# B36-V1_2.net
KiCad netlist of a schematic drawn in Altium Designer
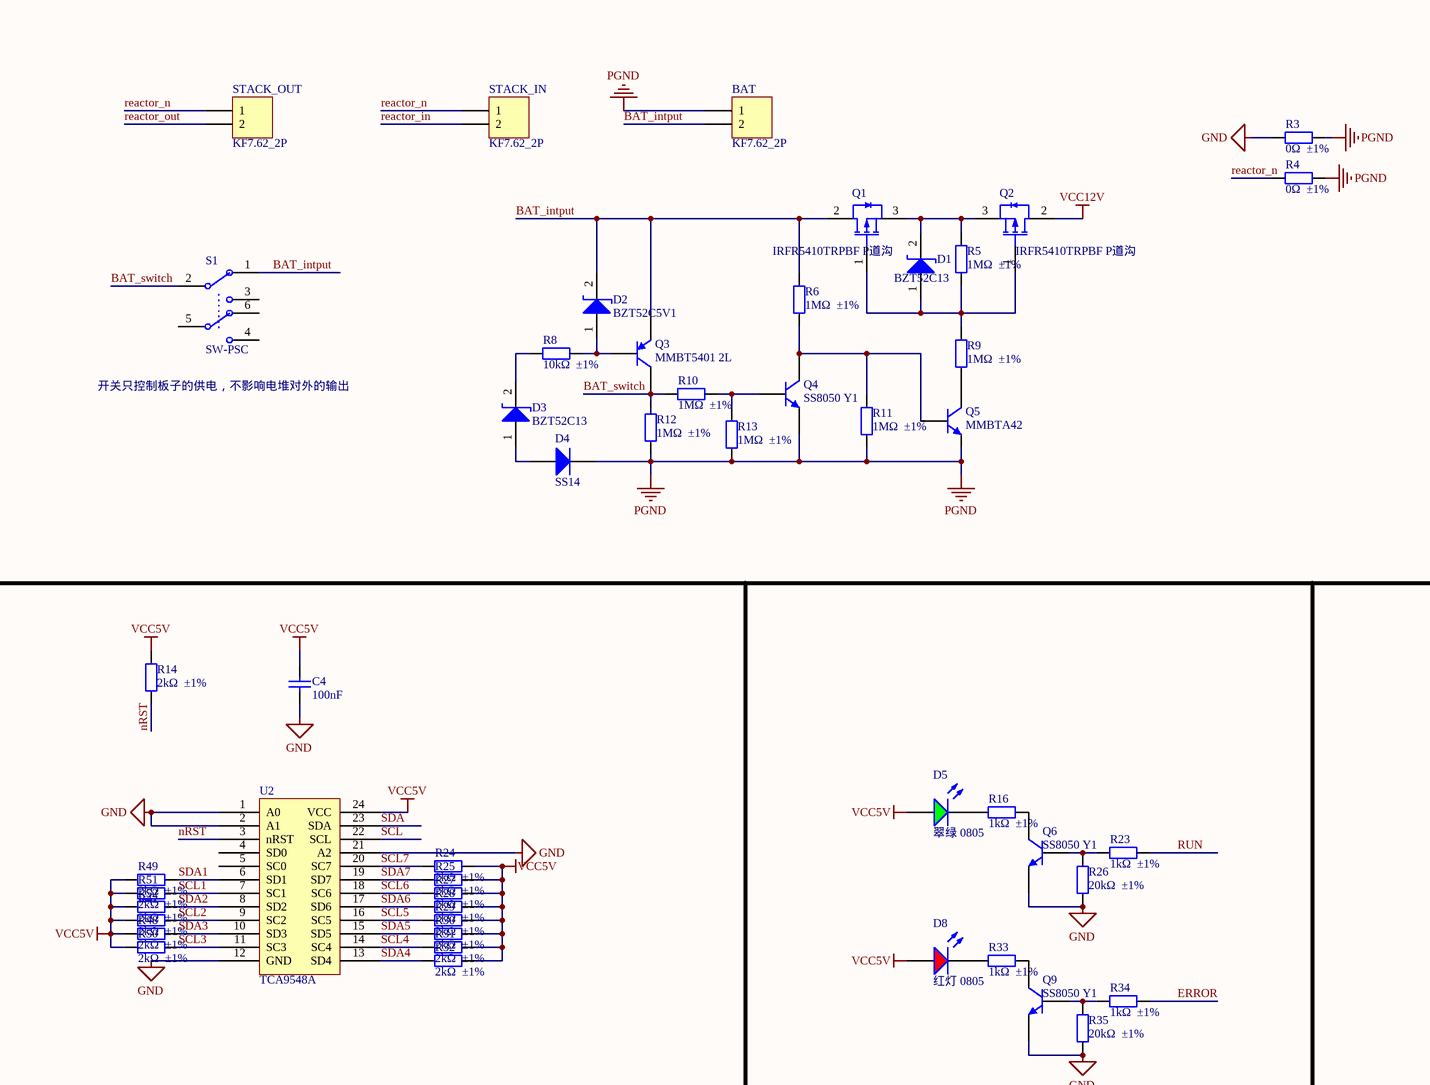
[diagram p0: B36-V1.2.SchDoc, top left]
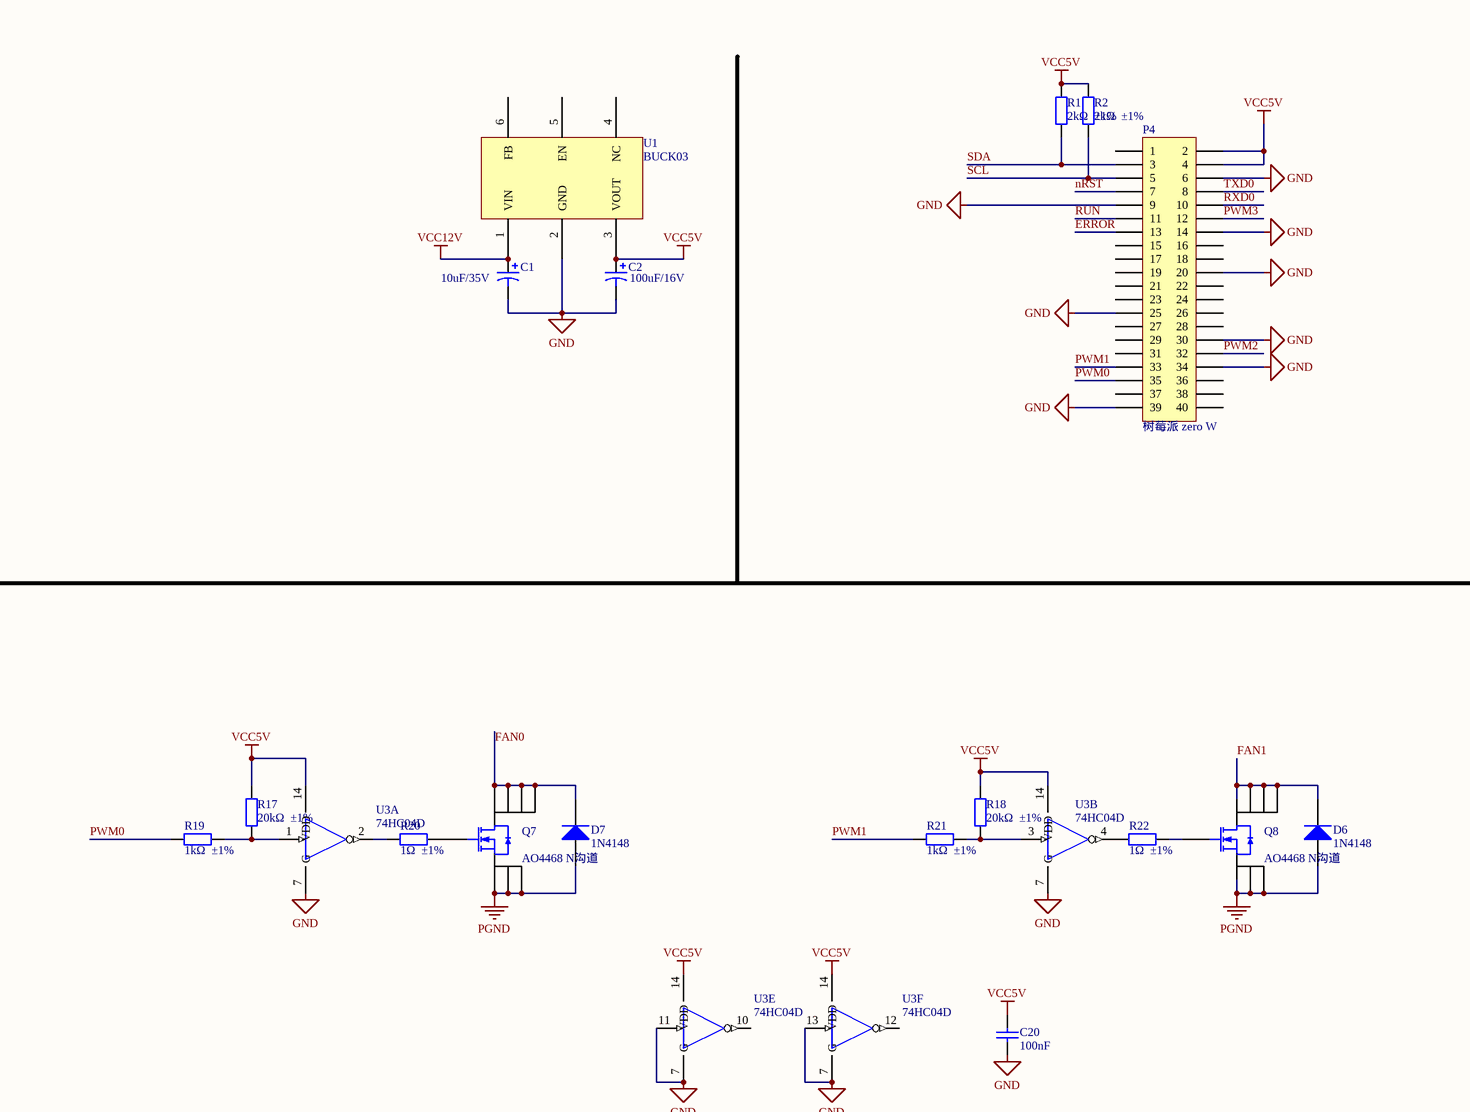
[diagram p1: B36-V1.2.SchDoc, top right]
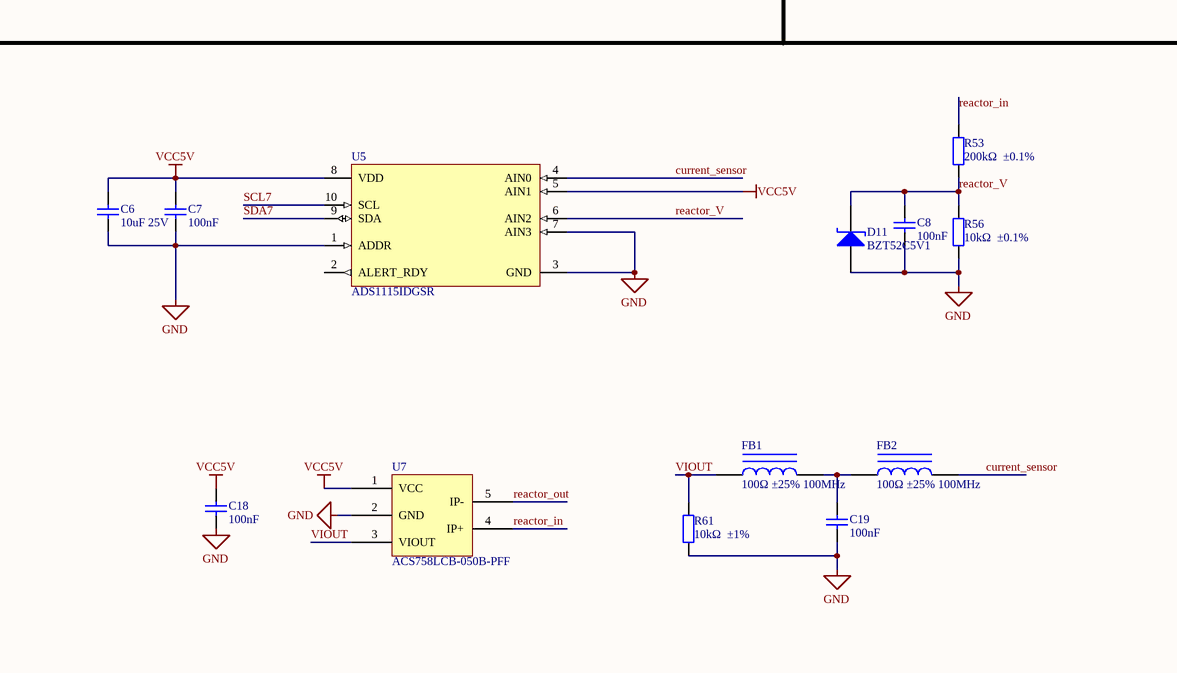
[diagram p2: B36-V1.2.SchDoc, bottom left]
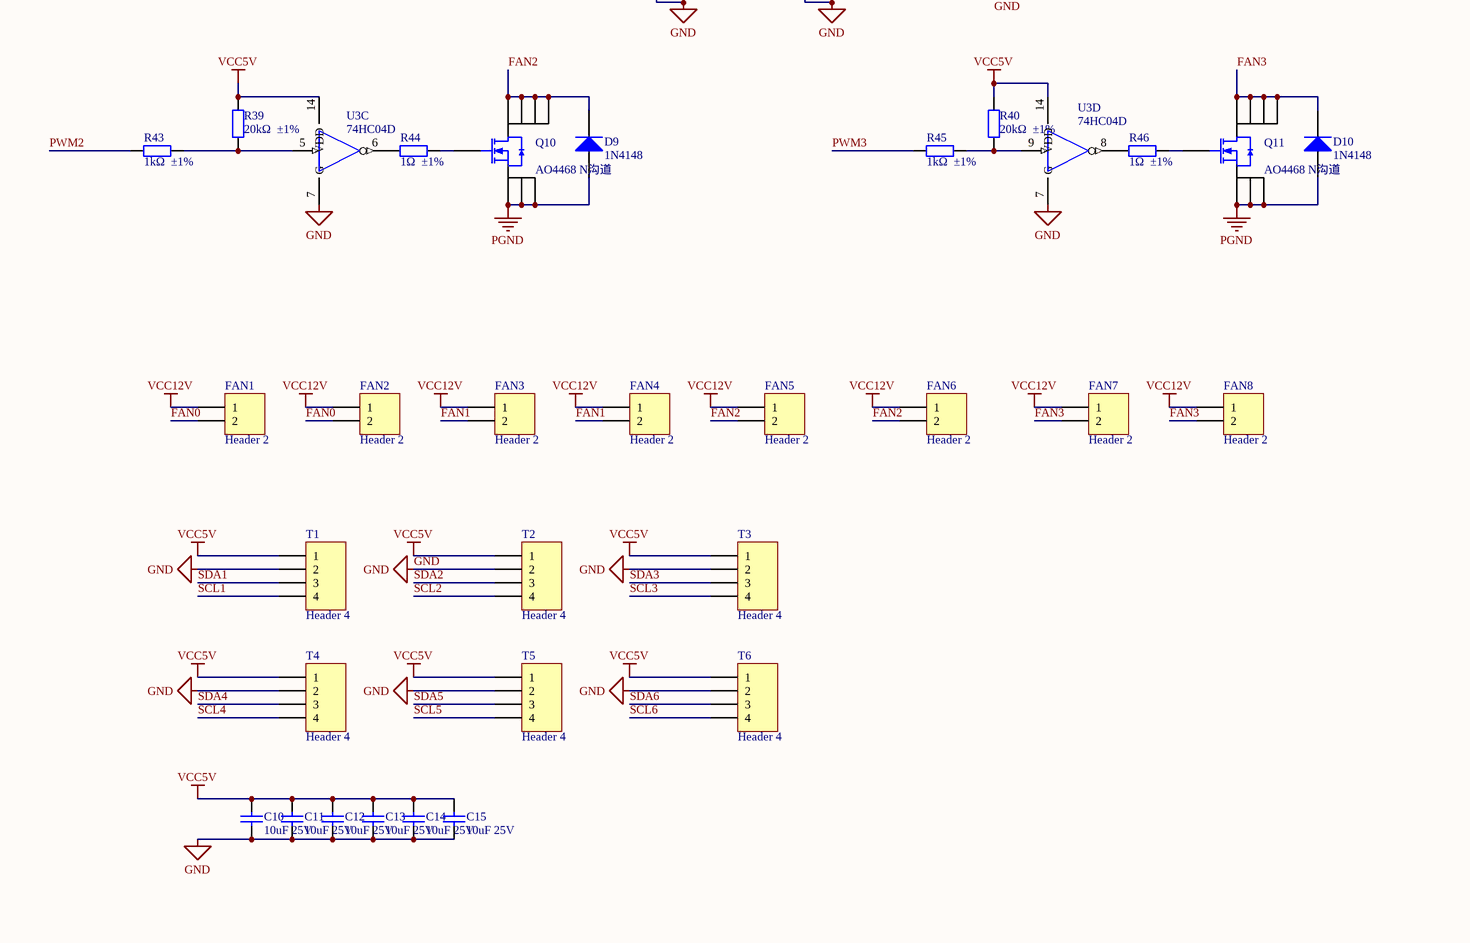
[diagram p3: B36-V1.2.SchDoc, bottom right]

(export (version "E")
  (design (tool "Eeschema 10.0.6"))
  (components
    (comp (ref "BAT")
      (value "KF7.62_2P")
      (footprint "KF7.62_2P")
      (description "Header, 2-Pin")
      (fields (field (name "PUBLISHER") "Altium Limited"))
      (libsource (lib "Miscellaneous Connectors") (part "Header 2"))
    )
    (comp (ref "C1")
      (value "10uF/35V")
      (footprint "CASE-C_6032")
      (description "Polarized Capacitor (Radial)")
      (fields (field (name "PUBLISHER") "Altium Limited"))
      (libsource (lib "MainBoard") (part "Cap Pol1"))
    )
    (comp (ref "C2")
      (value "100uF/16V")
      (footprint "CASE-C_6032")
      (description "Polarized Capacitor (Radial)")
      (fields (field (name "PUBLISHER") "Altium Limited"))
      (libsource (lib "MainBoard") (part "Cap Pol1"))
    )
    (comp (ref "C4")
      (value "100nF")
      (footprint "0603_C")
      (description "贴片电容")
      (libsource (lib "Cap") (part "0603 1.0pF (010) 0.25pF 50V"))
    )
    (comp (ref "C6")
      (value "10uF 25V")
      (footprint "0603_C")
      (description "贴片电容")
      (libsource (lib "Cap") (part "0805 6.8nF (682) 10% 50V"))
    )
    (comp (ref "C7")
      (value "100nF")
      (footprint "0603_C")
      (description "贴片电容")
      (libsource (lib "Cap") (part "0603 1.0pF (010) 0.25pF 50V"))
    )
    (comp (ref "C8")
      (value "100nF")
      (footprint "0603_C")
      (description "贴片电容")
      (libsource (lib "Cap") (part "0603 1.0pF (010) 0.25pF 50V"))
    )
    (comp (ref "C10")
      (value "10uF 25V")
      (footprint "0805_C")
      (description "贴片电容")
      (libsource (lib "Cap") (part "0805 6.8nF (682) 10% 50V"))
    )
    (comp (ref "C11")
      (value "10uF 25V")
      (footprint "0805_C")
      (description "贴片电容")
      (libsource (lib "Cap") (part "0805 6.8nF (682) 10% 50V"))
    )
    (comp (ref "C12")
      (value "10uF 25V")
      (footprint "0805_C")
      (description "贴片电容")
      (libsource (lib "Cap") (part "0805 6.8nF (682) 10% 50V"))
    )
    (comp (ref "C13")
      (value "10uF 25V")
      (footprint "0805_C")
      (description "贴片电容")
      (libsource (lib "Cap") (part "0805 6.8nF (682) 10% 50V"))
    )
    (comp (ref "C14")
      (value "10uF 25V")
      (footprint "0805_C")
      (description "贴片电容")
      (libsource (lib "Cap") (part "0805 6.8nF (682) 10% 50V"))
    )
    (comp (ref "C15")
      (value "10uF 25V")
      (footprint "0805_C")
      (description "贴片电容")
      (libsource (lib "Cap") (part "0805 6.8nF (682) 10% 50V"))
    )
    (comp (ref "C18")
      (value "100nF")
      (footprint "0603_C")
      (description "贴片电容")
      (libsource (lib "Cap") (part "0603 1.0pF (010) 0.25pF 50V"))
    )
    (comp (ref "C19")
      (value "100nF")
      (footprint "0603_C")
      (description "贴片电容")
      (libsource (lib "Cap") (part "0603 1.0pF (010) 0.25pF 50V"))
    )
    (comp (ref "C20")
      (value "100nF")
      (footprint "0603_C")
      (description "贴片电容")
      (libsource (lib "Cap") (part "0603 1.0pF (010) 0.25pF 50V"))
    )
    (comp (ref "D1")
      (value "BZT52C13")
      (footprint "sod-123")
      (description "稳压二极管")
      (fields (field (name "PUBLISHER") "Altium Limited"))
      (libsource (lib "Diode") (part "Diode-Z"))
    )
    (comp (ref "D2")
      (value "BZT52C5V1")
      (footprint "sod-123")
      (description "稳压二极管")
      (fields (field (name "PUBLISHER") "Altium Limited"))
      (libsource (lib "Diode") (part "Diode-Z"))
    )
    (comp (ref "D3")
      (value "BZT52C13")
      (footprint "sod-123")
      (description "稳压二极管")
      (fields (field (name "PUBLISHER") "Altium Limited"))
      (libsource (lib "Diode") (part "Diode-Z"))
    )
    (comp (ref "D4")
      (value "SS14")
      (footprint "sod-123")
      (description "二极管")
      (libsource (lib "Diode") (part "SMA(DO-214AC) SS54"))
    )
    (comp (ref "D5")
      (value "翠绿 0805")
      (footprint "0805_LED_S1")
      (description "发光二极管")
      (libsource (lib "LED") (part "0805 翠绿"))
    )
    (comp (ref "D6")
      (value "1N4148")
      (footprint "SOD-123")
      (description "肖特基二极管")
      (libsource (lib "Diode") (part "SOD-123 B5819W  SL"))
    )
    (comp (ref "D7")
      (value "1N4148")
      (footprint "SOD-123")
      (description "肖特基二极管")
      (libsource (lib "Diode") (part "SOD-123 B5819W  SL"))
    )
    (comp (ref "D8")
      (value "红灯 0805")
      (footprint "0805_LED_S1")
      (description "发光二极管")
      (libsource (lib "LED") (part "0805 红灯"))
    )
    (comp (ref "D9")
      (value "1N4148")
      (footprint "SOD-123")
      (description "肖特基二极管")
      (libsource (lib "Diode") (part "SOD-123 B5819W  SL"))
    )
    (comp (ref "D10")
      (value "1N4148")
      (footprint "SOD-123")
      (description "肖特基二极管")
      (libsource (lib "Diode") (part "SOD-123 B5819W  SL"))
    )
    (comp (ref "D11")
      (value "BZT52C5V1")
      (footprint "sod-123")
      (description "稳压二极管")
      (fields (field (name "PUBLISHER") "Altium Limited"))
      (libsource (lib "") (part "Diode-Z_1"))
    )
    (comp (ref "FAN1")
      (value "Header 2")
      (footprint "xh2.54_2p")
      (description "Header, 2-Pin")
      (fields (field (name "PUBLISHER") "Altium Limited"))
      (libsource (lib "Miscellaneous Connectors") (part "Header 2"))
    )
    (comp (ref "FAN2")
      (value "Header 2")
      (footprint "xh2.54_2p")
      (description "Header, 2-Pin")
      (fields (field (name "PUBLISHER") "Altium Limited"))
      (libsource (lib "Miscellaneous Connectors") (part "Header 2"))
    )
    (comp (ref "FAN3")
      (value "Header 2")
      (footprint "xh2.54_2p")
      (description "Header, 2-Pin")
      (fields (field (name "PUBLISHER") "Altium Limited"))
      (libsource (lib "Miscellaneous Connectors") (part "Header 2"))
    )
    (comp (ref "FAN4")
      (value "Header 2")
      (footprint "xh2.54_2p")
      (description "Header, 2-Pin")
      (fields (field (name "PUBLISHER") "Altium Limited"))
      (libsource (lib "Miscellaneous Connectors") (part "Header 2"))
    )
    (comp (ref "FAN5")
      (value "Header 2")
      (footprint "xh2.54_2p")
      (description "Header, 2-Pin")
      (fields (field (name "PUBLISHER") "Altium Limited"))
      (libsource (lib "Miscellaneous Connectors") (part "Header 2"))
    )
    (comp (ref "FAN6")
      (value "Header 2")
      (footprint "xh2.54_2p")
      (description "Header, 2-Pin")
      (fields (field (name "PUBLISHER") "Altium Limited"))
      (libsource (lib "Miscellaneous Connectors") (part "Header 2"))
    )
    (comp (ref "FAN7")
      (value "Header 2")
      (footprint "xh2.54_2p")
      (description "Header, 2-Pin")
      (fields (field (name "PUBLISHER") "Altium Limited"))
      (libsource (lib "Miscellaneous Connectors") (part "Header 2"))
    )
    (comp (ref "FAN8")
      (value "Header 2")
      (footprint "xh2.54_2p")
      (description "Header, 2-Pin")
      (fields (field (name "PUBLISHER") "Altium Limited"))
      (libsource (lib "Miscellaneous Connectors") (part "Header 2"))
    )
    (comp (ref "FB1")
      (value "100Ω ±25% 100MHz")
      (footprint "0805_L")
      (description "贴片磁珠")
      (libsource (lib "IUD") (part "0805 100Ω 25% 100MHz"))
    )
    (comp (ref "FB2")
      (value "100Ω ±25% 100MHz")
      (footprint "0805_L")
      (description "贴片磁珠")
      (libsource (lib "IUD") (part "0805 100Ω 25% 100MHz"))
    )
    (comp (ref "P4")
      (value "树莓派 zero W")
      (footprint "ZERO_W")
      (description "Header, 20-Pin, Dual row")
      (fields (field (name "PUBLISHER") "Altium Limited"))
      (libsource (lib "Miscellaneous Connectors") (part "Header 20X2"))
    )
    (comp (ref "Q1")
      (value "IRFR5410TRPBF P道沟")
      (footprint "to-252-2")
      (description "MOS(场效应管)")
      (libsource (lib "MOS") (part "AOD4185L P道沟"))
    )
    (comp (ref "Q2")
      (value "IRFR5410TRPBF P道沟")
      (footprint "to-252-2")
      (description "MOS(场效应管)")
      (libsource (lib "MOS") (part "AOD4185L P道沟"))
    )
    (comp (ref "Q3")
      (value "MMBT5401 2L")
      (footprint "SOT-23-3L")
      (description "三极管")
      (libsource (lib "Transistor_PNP") (part "SOT-23 MMBT5401 2L"))
    )
    (comp (ref "Q4")
      (value "SS8050 Y1")
      (footprint "SOT-23(SOT-23-3)")
      (description "三极管")
      (libsource (lib "Transistor_NPN") (part "SOT-23 SS8050 Y1"))
    )
    (comp (ref "Q5")
      (value "MMBTA42")
      (footprint "SOT-23(SOT-23-3)")
      (description "三极管")
      (libsource (lib "Transistor_NPN") (part "SOT-23 SS8050 Y1"))
    )
    (comp (ref "Q6")
      (value "SS8050 Y1")
      (footprint "SOT-23(SOT-23-3)")
      (description "三极管")
      (libsource (lib "Transistor_NPN") (part "SOT-23 SS8050 Y1"))
    )
    (comp (ref "Q7")
      (value "AO4468 N沟道")
      (footprint "SOIC-8_150mil")
      (description "MOS(场效应管)")
      (libsource (lib "MOS") (part "AO4468 N沟道"))
    )
    (comp (ref "Q8")
      (value "AO4468 N沟道")
      (footprint "SOIC-8_150mil")
      (description "MOS(场效应管)")
      (libsource (lib "MOS") (part "AO4468 N沟道"))
    )
    (comp (ref "Q9")
      (value "SS8050 Y1")
      (footprint "SOT-23(SOT-23-3)")
      (description "三极管")
      (libsource (lib "Transistor_NPN") (part "SOT-23 SS8050 Y1"))
    )
    (comp (ref "Q10")
      (value "AO4468 N沟道")
      (footprint "SOIC-8_150mil")
      (description "MOS(场效应管)")
      (libsource (lib "MOS") (part "AO4468 N沟道"))
    )
    (comp (ref "Q11")
      (value "AO4468 N沟道")
      (footprint "SOIC-8_150mil")
      (description "MOS(场效应管)")
      (libsource (lib "MOS") (part "AO4468 N沟道"))
    )
    (comp (ref "R1")
      (value "2kΩ  ±1%")
      (footprint "0603_R")
      (description "贴片电阻")
      (libsource (lib "") (part "0603 1Ω (1R00) 1%_1"))
    )
    (comp (ref "R2")
      (value "2kΩ  ±1%")
      (footprint "0603_R")
      (description "贴片电阻")
      (libsource (lib "") (part "0603 1Ω (1R00) 1%_1"))
    )
    (comp (ref "R3")
      (value "0Ω  ±1%")
      (footprint "0603_R")
      (description "贴片电阻")
      (libsource (lib "") (part "0603 1Ω (1R00) 1%_3"))
    )
    (comp (ref "R4")
      (value "0Ω  ±1%")
      (footprint "0603_R")
      (description "贴片电阻")
      (libsource (lib "") (part "0603 1Ω (1R00) 1%_3"))
    )
    (comp (ref "R5")
      (value "1MΩ  ±1%")
      (footprint "0603_R")
      (description "贴片电阻")
      (libsource (lib "RES") (part "0603 1MΩ (1004) 1%"))
    )
    (comp (ref "R6")
      (value "1MΩ  ±1%")
      (footprint "0603_R")
      (description "贴片电阻")
      (libsource (lib "RES") (part "0603 1MΩ (1004) 1%"))
    )
    (comp (ref "R8")
      (value "10kΩ  ±1%")
      (footprint "0603_R")
      (description "贴片电阻")
      (libsource (lib "") (part "0603 1Ω (1R00) 1%_2"))
    )
    (comp (ref "R9")
      (value "1MΩ  ±1%")
      (footprint "0603_R")
      (description "贴片电阻")
      (libsource (lib "RES") (part "0603 1MΩ (1004) 1%"))
    )
    (comp (ref "R10")
      (value "1MΩ  ±1%")
      (footprint "0603_R")
      (description "贴片电阻")
      (libsource (lib "") (part "0603 1MΩ (1004) 1%_1"))
    )
    (comp (ref "R11")
      (value "1MΩ  ±1%")
      (footprint "0603_R")
      (description "贴片电阻")
      (libsource (lib "RES") (part "0603 1MΩ (1004) 1%"))
    )
    (comp (ref "R12")
      (value "1MΩ  ±1%")
      (footprint "0603_R")
      (description "贴片电阻")
      (libsource (lib "RES") (part "0805 1MΩ (1004) 1%"))
    )
    (comp (ref "R13")
      (value "1MΩ  ±1%")
      (footprint "0603_R")
      (description "贴片电阻")
      (libsource (lib "RES") (part "0603 1MΩ (1004) 1%"))
    )
    (comp (ref "R14")
      (value "2kΩ  ±1%")
      (footprint "0603_R")
      (description "贴片电阻")
      (libsource (lib "") (part "0603 1Ω (1R00) 1%_1"))
    )
    (comp (ref "R16")
      (value "1kΩ  ±1%")
      (footprint "0603_R")
      (description "贴片电阻")
      (libsource (lib "") (part "0603 1Ω (1R00) 1%_2"))
    )
    (comp (ref "R17")
      (value "20kΩ  ±1%")
      (footprint "0603_R")
      (description "贴片电阻")
      (libsource (lib "") (part "0603 1Ω (1R00) 1%_1"))
    )
    (comp (ref "R18")
      (value "20kΩ  ±1%")
      (footprint "0603_R")
      (description "贴片电阻")
      (libsource (lib "") (part "0603 1Ω (1R00) 1%_1"))
    )
    (comp (ref "R19")
      (value "1kΩ  ±1%")
      (footprint "0603_R")
      (description "贴片电阻")
      (libsource (lib "") (part "0603 1Ω (1R00) 1%_2"))
    )
    (comp (ref "R20")
      (value "1Ω  ±1%")
      (footprint "0603_R")
      (description "贴片电阻")
      (libsource (lib "") (part "0603 1Ω (1R00) 1%_3"))
    )
    (comp (ref "R21")
      (value "1kΩ  ±1%")
      (footprint "0603_R")
      (description "贴片电阻")
      (libsource (lib "") (part "0603 1Ω (1R00) 1%_2"))
    )
    (comp (ref "R22")
      (value "1Ω  ±1%")
      (footprint "0603_R")
      (description "贴片电阻")
      (libsource (lib "") (part "0603 1Ω (1R00) 1%_3"))
    )
    (comp (ref "R23")
      (value "1kΩ  ±1%")
      (footprint "0603_R")
      (description "贴片电阻")
      (libsource (lib "") (part "0603 1Ω (1R00) 1%_2"))
    )
    (comp (ref "R24")
      (value "2kΩ  ±1%")
      (footprint "0603_R")
      (description "贴片电阻")
      (libsource (lib "RES") (part "0603 1Ω (1R00) 1%"))
    )
    (comp (ref "R25")
      (value "2kΩ  ±1%")
      (footprint "0603_R")
      (description "贴片电阻")
      (libsource (lib "RES") (part "0603 1Ω (1R00) 1%"))
    )
    (comp (ref "R26")
      (value "20kΩ  ±1%")
      (footprint "0603_R")
      (description "贴片电阻")
      (libsource (lib "") (part "0603 1Ω (1R00) 1%_1"))
    )
    (comp (ref "R27")
      (value "2kΩ  ±1%")
      (footprint "0603_R")
      (description "贴片电阻")
      (libsource (lib "RES") (part "0603 1Ω (1R00) 1%"))
    )
    (comp (ref "R28")
      (value "2kΩ  ±1%")
      (footprint "0603_R")
      (description "贴片电阻")
      (libsource (lib "RES") (part "0603 1Ω (1R00) 1%"))
    )
    (comp (ref "R29")
      (value "2kΩ  ±1%")
      (footprint "0603_R")
      (description "贴片电阻")
      (libsource (lib "RES") (part "0603 1Ω (1R00) 1%"))
    )
    (comp (ref "R30")
      (value "2kΩ  ±1%")
      (footprint "0603_R")
      (description "贴片电阻")
      (libsource (lib "RES") (part "0603 1Ω (1R00) 1%"))
    )
    (comp (ref "R31")
      (value "2kΩ  ±1%")
      (footprint "0603_R")
      (description "贴片电阻")
      (libsource (lib "RES") (part "0603 1Ω (1R00) 1%"))
    )
    (comp (ref "R32")
      (value "2kΩ  ±1%")
      (footprint "0603_R")
      (description "贴片电阻")
      (libsource (lib "RES") (part "0603 1Ω (1R00) 1%"))
    )
    (comp (ref "R33")
      (value "1kΩ  ±1%")
      (footprint "0603_R")
      (description "贴片电阻")
      (libsource (lib "") (part "0603 1Ω (1R00) 1%_2"))
    )
    (comp (ref "R34")
      (value "1kΩ  ±1%")
      (footprint "0603_R")
      (description "贴片电阻")
      (libsource (lib "") (part "0603 1Ω (1R00) 1%_2"))
    )
    (comp (ref "R35")
      (value "20kΩ  ±1%")
      (footprint "0603_R")
      (description "贴片电阻")
      (libsource (lib "") (part "0603 1Ω (1R00) 1%_1"))
    )
    (comp (ref "R39")
      (value "20kΩ  ±1%")
      (footprint "0603_R")
      (description "贴片电阻")
      (libsource (lib "") (part "0603 1Ω (1R00) 1%_1"))
    )
    (comp (ref "R40")
      (value "20kΩ  ±1%")
      (footprint "0603_R")
      (description "贴片电阻")
      (libsource (lib "") (part "0603 1Ω (1R00) 1%_1"))
    )
    (comp (ref "R42")
      (value "2kΩ  ±1%")
      (footprint "0603_R")
      (description "贴片电阻")
      (libsource (lib "RES") (part "0603 1Ω (1R00) 1%"))
    )
    (comp (ref "R43")
      (value "1kΩ  ±1%")
      (footprint "0603_R")
      (description "贴片电阻")
      (libsource (lib "") (part "0603 1Ω (1R00) 1%_2"))
    )
    (comp (ref "R44")
      (value "1Ω  ±1%")
      (footprint "0603_R")
      (description "贴片电阻")
      (libsource (lib "") (part "0603 1Ω (1R00) 1%_3"))
    )
    (comp (ref "R45")
      (value "1kΩ  ±1%")
      (footprint "0603_R")
      (description "贴片电阻")
      (libsource (lib "") (part "0603 1Ω (1R00) 1%_2"))
    )
    (comp (ref "R46")
      (value "1Ω  ±1%")
      (footprint "0603_R")
      (description "贴片电阻")
      (libsource (lib "") (part "0603 1Ω (1R00) 1%_3"))
    )
    (comp (ref "R48")
      (value "2kΩ  ±1%")
      (footprint "0603_R")
      (description "贴片电阻")
      (libsource (lib "") (part "0603 1Ω (1R00) 1%_1"))
    )
    (comp (ref "R49")
      (value "2kΩ  ±1%")
      (footprint "0603_R")
      (description "贴片电阻")
      (libsource (lib "RES") (part "0603 1Ω (1R00) 1%"))
    )
    (comp (ref "R50")
      (value "2kΩ  ±1%")
      (footprint "0603_R")
      (description "贴片电阻")
      (libsource (lib "") (part "0603 1Ω (1R00) 1%_1"))
    )
    (comp (ref "R51")
      (value "2kΩ  ±1%")
      (footprint "0603_R")
      (description "贴片电阻")
      (libsource (lib "RES") (part "0603 1Ω (1R00) 1%"))
    )
    (comp (ref "R52")
      (value "2kΩ  ±1%")
      (footprint "0603_R")
      (description "贴片电阻")
      (libsource (lib "RES") (part "0603 1Ω (1R00) 1%"))
    )
    (comp (ref "R53")
      (value "200kΩ  ±0.1%")
      (footprint "0603_R")
      (description "贴片电阻")
      (libsource (lib "") (part "0603 1Ω (1R00) 1%_1"))
    )
    (comp (ref "R56")
      (value "10kΩ  ±0.1%")
      (footprint "0603_R")
      (description "贴片电阻")
      (libsource (lib "") (part "0603 1Ω (1R00) 1%_1"))
    )
    (comp (ref "R61")
      (value "10kΩ  ±1%")
      (footprint "0603_R")
      (description "贴片电阻")
      (libsource (lib "") (part "0603 1Ω (1R00) 1%_1"))
    )
    (comp (ref "S1")
      (value "SW-PSC")
      (footprint "PCB:SW_PSC")
      (description "自锁开关 两侧 6脚")
      (fields (field (name "PUBLISHER") "Altium Limited"))
      (libsource (lib "fszhang") (part "SW-PSC"))
    )
    (comp (ref "STACK_IN")
      (value "KF7.62_2P")
      (footprint "KF7.62_2P")
      (description "Header, 2-Pin")
      (fields (field (name "PUBLISHER") "Altium Limited"))
      (libsource (lib "Miscellaneous Connectors") (part "Header 2"))
    )
    (comp (ref "STACK_OUT")
      (value "KF7.62_2P")
      (footprint "KF7.62_2P")
      (description "Header, 2-Pin")
      (fields (field (name "PUBLISHER") "Altium Limited"))
      (libsource (lib "Miscellaneous Connectors") (part "Header 2"))
    )
    (comp (ref "T1")
      (value "Header 4")
      (footprint "xh1.25_4p")
      (description "Header, 4-Pin")
      (fields (field (name "PUBLISHER") "Altium Limited"))
      (libsource (lib "Miscellaneous Connectors") (part "Header 4"))
    )
    (comp (ref "T2")
      (value "Header 4")
      (footprint "xh1.25_4p")
      (description "Header, 4-Pin")
      (fields (field (name "PUBLISHER") "Altium Limited"))
      (libsource (lib "Miscellaneous Connectors") (part "Header 4"))
    )
    (comp (ref "T3")
      (value "Header 4")
      (footprint "xh1.25_4p")
      (description "Header, 4-Pin")
      (fields (field (name "PUBLISHER") "Altium Limited"))
      (libsource (lib "Miscellaneous Connectors") (part "Header 4"))
    )
    (comp (ref "T4")
      (value "Header 4")
      (footprint "xh1.25_4p")
      (description "Header, 4-Pin")
      (fields (field (name "PUBLISHER") "Altium Limited"))
      (libsource (lib "Miscellaneous Connectors") (part "Header 4"))
    )
    (comp (ref "T5")
      (value "Header 4")
      (footprint "xh1.25_4p")
      (description "Header, 4-Pin")
      (fields (field (name "PUBLISHER") "Altium Limited"))
      (libsource (lib "Miscellaneous Connectors") (part "Header 4"))
    )
    (comp (ref "T6")
      (value "Header 4")
      (footprint "xh1.25_4p")
      (description "Header, 4-Pin")
      (fields (field (name "PUBLISHER") "Altium Limited"))
      (libsource (lib "Miscellaneous Connectors") (part "Header 4"))
    )
    (comp (ref "U1")
      (value "BUCK03")
      (footprint "BUCK03-2")
      (description "引出FB和EN的迷你型5V4A模块")
      (libsource (lib "CKCY") (part "BUCK03"))
    )
    (comp (ref "U2") (value "TCA9548A") (footprint "TSSOP-24") (libsource (lib "Schlib1") (part "TCA9548A")))
    (comp (ref "U3")
      (value "74HC04D")
      (footprint "SOIC-14_150mil")
      (description "74系列逻辑芯片")
      (libsource (lib "IC") (part "74HC04D_[C5590]"))
    )
    (comp (ref "U5")
      (value "ADS1115IDGSR")
      (footprint "MSOP-10")
      (description "Imported")
      (fields (field (name "MANUFACTURER") "Texas Instruments"))
      (libsource (lib "SCH") (part "ADS1115IDGSR"))
    )
    (comp (ref "U7") (value "ACS758LCB-050B-PFF") (footprint "PFF") (libsource (lib "SCH") (part "ACS758")))
  )
  (nets
    (net (code "1") (name "/BAT_intput") (class "Default")
      (node (ref "BAT") (pin "2") (pinfunction "2_2") (pintype "passive"))
      (node (ref "D2") (pin "2") (pinfunction "K_2") (pintype "passive"))
      (node (ref "Q1") (pin "2") (pinfunction "D_2") (pintype "passive"))
      (node (ref "Q3") (pin "2") (pinfunction "E_2") (pintype "passive"))
      (node (ref "R6") (pin "2") (pinfunction "2_2") (pintype "passive"))
      (node (ref "S1") (pin "1") (pinfunction "1_1") (pintype "passive"))
    )
    (net (code "2") (name "/BAT_switch") (class "Default")
      (node (ref "Q3") (pin "3") (pinfunction "C_3") (pintype "passive"))
      (node (ref "R10") (pin "2") (pinfunction "2_2") (pintype "passive"))
      (node (ref "R12") (pin "1") (pinfunction "1_1") (pintype "passive"))
      (node (ref "S1") (pin "2") (pinfunction "2_2") (pintype "passive"))
    )
    (net (code "3") (name "/ERROR") (class "Default")
      (node (ref "P4") (pin "13") (pinfunction "13_13") (pintype "passive"))
      (node (ref "R34") (pin "1") (pinfunction "1_1") (pintype "passive"))
    )
    (net (code "4") (name "/FAN0") (class "Default")
      (node (ref "D7") (pin "2") (pinfunction "K_2") (pintype "passive"))
      (node (ref "FAN1") (pin "2") (pinfunction "2_2") (pintype "passive"))
      (node (ref "FAN2") (pin "2") (pinfunction "2_2") (pintype "passive"))
      (node (ref "Q7") (pin "5") (pinfunction "D_5") (pintype "passive"))
      (node (ref "Q7") (pin "6") (pinfunction "D_6") (pintype "passive"))
      (node (ref "Q7") (pin "7") (pinfunction "D_7") (pintype "passive"))
      (node (ref "Q7") (pin "8") (pinfunction "D_8") (pintype "passive"))
    )
    (net (code "5") (name "/FAN1") (class "Default")
      (node (ref "D6") (pin "2") (pinfunction "K_2") (pintype "passive"))
      (node (ref "FAN3") (pin "2") (pinfunction "2_2") (pintype "passive"))
      (node (ref "FAN4") (pin "2") (pinfunction "2_2") (pintype "passive"))
      (node (ref "Q8") (pin "5") (pinfunction "D_5") (pintype "passive"))
      (node (ref "Q8") (pin "6") (pinfunction "D_6") (pintype "passive"))
      (node (ref "Q8") (pin "7") (pinfunction "D_7") (pintype "passive"))
      (node (ref "Q8") (pin "8") (pinfunction "D_8") (pintype "passive"))
    )
    (net (code "6") (name "/FAN2") (class "Default")
      (node (ref "D9") (pin "2") (pinfunction "K_2") (pintype "passive"))
      (node (ref "FAN5") (pin "2") (pinfunction "2_2") (pintype "passive"))
      (node (ref "FAN6") (pin "2") (pinfunction "2_2") (pintype "passive"))
      (node (ref "Q10") (pin "5") (pinfunction "D_5") (pintype "passive"))
      (node (ref "Q10") (pin "6") (pinfunction "D_6") (pintype "passive"))
      (node (ref "Q10") (pin "7") (pinfunction "D_7") (pintype "passive"))
      (node (ref "Q10") (pin "8") (pinfunction "D_8") (pintype "passive"))
    )
    (net (code "7") (name "/FAN3") (class "Default")
      (node (ref "D10") (pin "2") (pinfunction "K_2") (pintype "passive"))
      (node (ref "FAN7") (pin "2") (pinfunction "2_2") (pintype "passive"))
      (node (ref "FAN8") (pin "2") (pinfunction "2_2") (pintype "passive"))
      (node (ref "Q11") (pin "5") (pinfunction "D_5") (pintype "passive"))
      (node (ref "Q11") (pin "6") (pinfunction "D_6") (pintype "passive"))
      (node (ref "Q11") (pin "7") (pinfunction "D_7") (pintype "passive"))
      (node (ref "Q11") (pin "8") (pinfunction "D_8") (pintype "passive"))
    )
    (net (code "8") (name "/PWM0") (class "Default")
      (node (ref "P4") (pin "35") (pinfunction "35_35") (pintype "passive"))
      (node (ref "R19") (pin "2") (pinfunction "2_2") (pintype "passive"))
    )
    (net (code "9") (name "/PWM1") (class "Default")
      (node (ref "P4") (pin "33") (pinfunction "33_33") (pintype "passive"))
      (node (ref "R21") (pin "2") (pinfunction "2_2") (pintype "passive"))
    )
    (net (code "10") (name "/PWM2") (class "Default")
      (node (ref "P4") (pin "32") (pinfunction "32_32") (pintype "passive"))
      (node (ref "R43") (pin "2") (pinfunction "2_2") (pintype "passive"))
    )
    (net (code "11") (name "/PWM3") (class "Default")
      (node (ref "P4") (pin "12") (pinfunction "12_12") (pintype "passive"))
      (node (ref "R45") (pin "2") (pinfunction "2_2") (pintype "passive"))
    )
    (net (code "12") (name "/RUN") (class "Default")
      (node (ref "P4") (pin "11") (pinfunction "11_11") (pintype "passive"))
      (node (ref "R23") (pin "1") (pinfunction "1_1") (pintype "passive"))
    )
    (net (code "13") (name "/RXD0") (class "Default")
      (node (ref "P4") (pin "10") (pinfunction "10_10") (pintype "passive"))
    )
    (net (code "14") (name "/SCL") (class "Default")
      (node (ref "P4") (pin "5") (pinfunction "5_5") (pintype "passive"))
      (node (ref "R2") (pin "2") (pinfunction "2_2") (pintype "passive"))
      (node (ref "U2") (pin "22") (pinfunction "SCL_22") (pintype "passive"))
    )
    (net (code "15") (name "/SCL1") (class "Default")
      (node (ref "R51") (pin "2") (pinfunction "2_2") (pintype "passive"))
      (node (ref "T1") (pin "4") (pinfunction "4_4") (pintype "passive"))
      (node (ref "U2") (pin "7") (pinfunction "SC1_7") (pintype "passive"))
    )
    (net (code "16") (name "/SCL2") (class "Default")
      (node (ref "R42") (pin "2") (pinfunction "2_2") (pintype "passive"))
      (node (ref "T2") (pin "4") (pinfunction "4_4") (pintype "passive"))
      (node (ref "U2") (pin "9") (pinfunction "SC2_9") (pintype "passive"))
    )
    (net (code "17") (name "/SCL3") (class "Default")
      (node (ref "R50") (pin "1") (pinfunction "1_1") (pintype "passive"))
      (node (ref "T3") (pin "4") (pinfunction "4_4") (pintype "passive"))
      (node (ref "U2") (pin "11") (pinfunction "SC3_11") (pintype "passive"))
    )
    (net (code "18") (name "/SCL4") (class "Default")
      (node (ref "R31") (pin "1") (pinfunction "1_1") (pintype "passive"))
      (node (ref "T4") (pin "4") (pinfunction "4_4") (pintype "passive"))
      (node (ref "U2") (pin "14") (pinfunction "SC4_14") (pintype "passive"))
    )
    (net (code "19") (name "/SCL5") (class "Default")
      (node (ref "R29") (pin "1") (pinfunction "1_1") (pintype "passive"))
      (node (ref "T5") (pin "4") (pinfunction "4_4") (pintype "passive"))
      (node (ref "U2") (pin "16") (pinfunction "SC5_16") (pintype "passive"))
    )
    (net (code "20") (name "/SCL6") (class "Default")
      (node (ref "R27") (pin "1") (pinfunction "1_1") (pintype "passive"))
      (node (ref "T6") (pin "4") (pinfunction "4_4") (pintype "passive"))
      (node (ref "U2") (pin "18") (pinfunction "SC6_18") (pintype "passive"))
    )
    (net (code "21") (name "/SCL7") (class "Default")
      (node (ref "R24") (pin "1") (pinfunction "1_1") (pintype "passive"))
      (node (ref "U2") (pin "20") (pinfunction "SC7_20") (pintype "passive"))
      (node (ref "U5") (pin "10") (pinfunction "SCL_10") (pintype "input"))
    )
    (net (code "22") (name "/SDA") (class "Default")
      (node (ref "P4") (pin "3") (pinfunction "3_3") (pintype "passive"))
      (node (ref "R1") (pin "2") (pinfunction "2_2") (pintype "passive"))
      (node (ref "U2") (pin "23") (pinfunction "SDA_23") (pintype "passive"))
    )
    (net (code "23") (name "/SDA1") (class "Default")
      (node (ref "R49") (pin "2") (pinfunction "2_2") (pintype "passive"))
      (node (ref "T1") (pin "3") (pinfunction "3_3") (pintype "passive"))
      (node (ref "U2") (pin "6") (pinfunction "SD1_6") (pintype "passive"))
    )
    (net (code "24") (name "/SDA2") (class "Default")
      (node (ref "R52") (pin "2") (pinfunction "2_2") (pintype "passive"))
      (node (ref "T2") (pin "3") (pinfunction "3_3") (pintype "passive"))
      (node (ref "U2") (pin "8") (pinfunction "SD2_8") (pintype "passive"))
    )
    (net (code "25") (name "/SDA3") (class "Default")
      (node (ref "R48") (pin "1") (pinfunction "1_1") (pintype "passive"))
      (node (ref "T3") (pin "3") (pinfunction "3_3") (pintype "passive"))
      (node (ref "U2") (pin "10") (pinfunction "SD3_10") (pintype "passive"))
    )
    (net (code "26") (name "/SDA4") (class "Default")
      (node (ref "R32") (pin "1") (pinfunction "1_1") (pintype "passive"))
      (node (ref "T4") (pin "3") (pinfunction "3_3") (pintype "passive"))
      (node (ref "U2") (pin "13") (pinfunction "SD4_13") (pintype "passive"))
    )
    (net (code "27") (name "/SDA5") (class "Default")
      (node (ref "R30") (pin "1") (pinfunction "1_1") (pintype "passive"))
      (node (ref "T5") (pin "3") (pinfunction "3_3") (pintype "passive"))
      (node (ref "U2") (pin "15") (pinfunction "SD5_15") (pintype "passive"))
    )
    (net (code "28") (name "/SDA6") (class "Default")
      (node (ref "R28") (pin "1") (pinfunction "1_1") (pintype "passive"))
      (node (ref "T6") (pin "3") (pinfunction "3_3") (pintype "passive"))
      (node (ref "U2") (pin "17") (pinfunction "SD6_17") (pintype "passive"))
    )
    (net (code "29") (name "/SDA7") (class "Default")
      (node (ref "R25") (pin "1") (pinfunction "1_1") (pintype "passive"))
      (node (ref "U2") (pin "19") (pinfunction "SD7_19") (pintype "passive"))
      (node (ref "U5") (pin "9") (pinfunction "SDA_9") (pintype "bidirectional"))
    )
    (net (code "30") (name "/TXD0") (class "Default")
      (node (ref "P4") (pin "8") (pinfunction "8_8") (pintype "passive"))
    )
    (net (code "31") (name "/VIOUT") (class "Default")
      (node (ref "FB1") (pin "1") (pinfunction "1_1") (pintype "passive"))
      (node (ref "R61") (pin "1") (pinfunction "1_1") (pintype "passive"))
      (node (ref "U7") (pin "3") (pinfunction "VIOUT_3") (pintype "passive"))
    )
    (net (code "32") (name "/current_sensor") (class "Default")
      (node (ref "FB2") (pin "2") (pinfunction "2_2") (pintype "passive"))
      (node (ref "U5") (pin "4") (pinfunction "AIN0_4") (pintype "input"))
    )
    (net (code "33") (name "/nRST") (class "Default")
      (node (ref "P4") (pin "7") (pinfunction "7_7") (pintype "passive"))
      (node (ref "R14") (pin "2") (pinfunction "2_2") (pintype "passive"))
      (node (ref "U2") (pin "3") (pinfunction "nRST_3") (pintype "passive"))
    )
    (net (code "34") (name "/reactor_V") (class "Default")
      (node (ref "C8") (pin "2") (pinfunction "2_2") (pintype "passive"))
      (node (ref "D11") (pin "2") (pinfunction "K_2") (pintype "passive"))
      (node (ref "R53") (pin "2") (pinfunction "2_2") (pintype "passive"))
      (node (ref "R56") (pin "1") (pinfunction "1_1") (pintype "passive"))
      (node (ref "U5") (pin "6") (pinfunction "AIN2_6") (pintype "input"))
    )
    (net (code "35") (name "/reactor_in") (class "Default")
      (node (ref "R53") (pin "1") (pinfunction "1_1") (pintype "passive"))
      (node (ref "STACK_IN") (pin "2") (pinfunction "2_2") (pintype "passive"))
      (node (ref "U7") (pin "4") (pinfunction "IP+_4") (pintype "passive"))
    )
    (net (code "36") (name "/reactor_n") (class "Default")
      (node (ref "R4") (pin "1") (pinfunction "1_1") (pintype "passive"))
      (node (ref "STACK_IN") (pin "1") (pinfunction "1_1") (pintype "passive"))
      (node (ref "STACK_OUT") (pin "1") (pinfunction "1_1") (pintype "passive"))
    )
    (net (code "37") (name "/reactor_out") (class "Default")
      (node (ref "STACK_OUT") (pin "2") (pinfunction "2_2") (pintype "passive"))
      (node (ref "U7") (pin "5") (pinfunction "IP-_5") (pintype "passive"))
    )
    (net (code "38") (name "GND") (class "Default")
      (node (ref "C1") (pin "2") (pinfunction "2_2") (pintype "passive"))
      (node (ref "C10") (pin "1") (pinfunction "1_1") (pintype "passive"))
      (node (ref "C11") (pin "1") (pinfunction "1_1") (pintype "passive"))
      (node (ref "C12") (pin "1") (pinfunction "1_1") (pintype "passive"))
      (node (ref "C13") (pin "1") (pinfunction "1_1") (pintype "passive"))
      (node (ref "C14") (pin "1") (pinfunction "1_1") (pintype "passive"))
      (node (ref "C15") (pin "1") (pinfunction "1_1") (pintype "passive"))
      (node (ref "C18") (pin "1") (pinfunction "1_1") (pintype "passive"))
      (node (ref "C19") (pin "1") (pinfunction "1_1") (pintype "passive"))
      (node (ref "C2") (pin "2") (pinfunction "2_2") (pintype "passive"))
      (node (ref "C20") (pin "1") (pinfunction "1_1") (pintype "passive"))
      (node (ref "C4") (pin "1") (pinfunction "1_1") (pintype "passive"))
      (node (ref "C6") (pin "1") (pinfunction "1_1") (pintype "passive"))
      (node (ref "C7") (pin "1") (pinfunction "1_1") (pintype "passive"))
      (node (ref "C8") (pin "1") (pinfunction "1_1") (pintype "passive"))
      (node (ref "D11") (pin "1") (pinfunction "A_1") (pintype "passive"))
      (node (ref "P4") (pin "14") (pinfunction "14_14") (pintype "passive"))
      (node (ref "P4") (pin "20") (pinfunction "20_20") (pintype "passive"))
      (node (ref "P4") (pin "25") (pinfunction "25_25") (pintype "passive"))
      (node (ref "P4") (pin "30") (pinfunction "30_30") (pintype "passive"))
      (node (ref "P4") (pin "34") (pinfunction "34_34") (pintype "passive"))
      (node (ref "P4") (pin "39") (pinfunction "39_39") (pintype "passive"))
      (node (ref "P4") (pin "6") (pinfunction "6_6") (pintype "passive"))
      (node (ref "P4") (pin "9") (pinfunction "9_9") (pintype "passive"))
      (node (ref "Q6") (pin "2") (pinfunction "E_2") (pintype "passive"))
      (node (ref "Q9") (pin "2") (pinfunction "E_2") (pintype "passive"))
      (node (ref "R26") (pin "2") (pinfunction "2_2") (pintype "passive"))
      (node (ref "R3") (pin "1") (pinfunction "1_1") (pintype "passive"))
      (node (ref "R35") (pin "2") (pinfunction "2_2") (pintype "passive"))
      (node (ref "R56") (pin "2") (pinfunction "2_2") (pintype "passive"))
      (node (ref "R61") (pin "2") (pinfunction "2_2") (pintype "passive"))
      (node (ref "T1") (pin "2") (pinfunction "2_2") (pintype "passive"))
      (node (ref "T2") (pin "2") (pinfunction "2_2") (pintype "passive"))
      (node (ref "T3") (pin "2") (pinfunction "2_2") (pintype "passive"))
      (node (ref "T4") (pin "2") (pinfunction "2_2") (pintype "passive"))
      (node (ref "T5") (pin "2") (pinfunction "2_2") (pintype "passive"))
      (node (ref "T6") (pin "2") (pinfunction "2_2") (pintype "passive"))
      (node (ref "U1") (pin "2") (pinfunction "GND_2") (pintype "passive"))
      (node (ref "U2") (pin "1") (pinfunction "A0_1") (pintype "passive"))
      (node (ref "U2") (pin "12") (pinfunction "GND_12") (pintype "passive"))
      (node (ref "U2") (pin "2") (pinfunction "A1_2") (pintype "passive"))
      (node (ref "U2") (pin "21") (pinfunction "A2_21") (pintype "passive"))
      (node (ref "U3") (pin "11") (pinfunction "A_11") (pintype "input"))
      (node (ref "U3") (pin "13") (pinfunction "A_13") (pintype "input"))
      (node (ref "U3") (pin "7") (pinfunction "G_7") (pintype "power_in"))
      (node (ref "U5") (pin "1") (pinfunction "ADDR_1") (pintype "input"))
      (node (ref "U5") (pin "3") (pinfunction "GND_3") (pintype "power_in"))
      (node (ref "U5") (pin "7") (pinfunction "AIN3_7") (pintype "input"))
      (node (ref "U7") (pin "2") (pinfunction "GND_2") (pintype "passive"))
    )
    (net (code "39") (name "Net-(C19-Pad2)") (class "Default")
      (node (ref "C19") (pin "2") (pinfunction "2_2") (pintype "passive"))
      (node (ref "FB1") (pin "2") (pinfunction "2_2") (pintype "passive"))
      (node (ref "FB2") (pin "1") (pinfunction "1_1") (pintype "passive"))
    )
    (net (code "40") (name "Net-(D1-A)") (class "Default")
      (node (ref "D1") (pin "1") (pinfunction "A_1") (pintype "passive"))
      (node (ref "Q1") (pin "1") (pinfunction "G_1") (pintype "passive"))
      (node (ref "Q2") (pin "1") (pinfunction "G_1") (pintype "passive"))
      (node (ref "R5") (pin "1") (pinfunction "1_1") (pintype "passive"))
      (node (ref "R9") (pin "2") (pinfunction "2_2") (pintype "passive"))
    )
    (net (code "41") (name "Net-(D1-K)") (class "Default")
      (node (ref "D1") (pin "2") (pinfunction "K_2") (pintype "passive"))
      (node (ref "Q1") (pin "3") (pinfunction "S_3") (pintype "passive"))
      (node (ref "Q2") (pin "3") (pinfunction "S_3") (pintype "passive"))
      (node (ref "R5") (pin "2") (pinfunction "2_2") (pintype "passive"))
    )
    (net (code "42") (name "Net-(D2-A)") (class "Default")
      (node (ref "D2") (pin "1") (pinfunction "A_1") (pintype "passive"))
      (node (ref "Q3") (pin "1") (pinfunction "B_1") (pintype "passive"))
      (node (ref "R8") (pin "1") (pinfunction "1_1") (pintype "passive"))
    )
    (net (code "43") (name "Net-(D3-A)") (class "Default")
      (node (ref "D3") (pin "1") (pinfunction "A_1") (pintype "passive"))
      (node (ref "D4") (pin "1") (pinfunction "A_1") (pintype "passive"))
    )
    (net (code "44") (name "Net-(D3-K)") (class "Default")
      (node (ref "D3") (pin "2") (pinfunction "K_2") (pintype "passive"))
      (node (ref "R8") (pin "2") (pinfunction "2_2") (pintype "passive"))
    )
    (net (code "45") (name "Net-(D5-PadK)") (class "Default")
      (node (ref "D5") (pin "K") (pinfunction "K_K") (pintype "passive"))
      (node (ref "R16") (pin "2") (pinfunction "2_2") (pintype "passive"))
    )
    (net (code "46") (name "Net-(D8-PadK)") (class "Default")
      (node (ref "D8") (pin "K") (pinfunction "K_K") (pintype "passive"))
      (node (ref "R33") (pin "2") (pinfunction "2_2") (pintype "passive"))
    )
    (net (code "47") (name "Net-(Q4-B)") (class "Default")
      (node (ref "Q4") (pin "1") (pinfunction "B_1") (pintype "passive"))
      (node (ref "R10") (pin "1") (pinfunction "1_1") (pintype "passive"))
      (node (ref "R13") (pin "2") (pinfunction "2_2") (pintype "passive"))
    )
    (net (code "48") (name "Net-(Q4-C)") (class "Default")
      (node (ref "Q4") (pin "3") (pinfunction "C_3") (pintype "passive"))
      (node (ref "Q5") (pin "1") (pinfunction "B_1") (pintype "passive"))
      (node (ref "R11") (pin "2") (pinfunction "2_2") (pintype "passive"))
      (node (ref "R6") (pin "1") (pinfunction "1_1") (pintype "passive"))
    )
    (net (code "49") (name "Net-(Q5-C)") (class "Default")
      (node (ref "Q5") (pin "3") (pinfunction "C_3") (pintype "passive"))
      (node (ref "R9") (pin "1") (pinfunction "1_1") (pintype "passive"))
    )
    (net (code "50") (name "Net-(Q6-B)") (class "Default")
      (node (ref "Q6") (pin "1") (pinfunction "B_1") (pintype "passive"))
      (node (ref "R23") (pin "2") (pinfunction "2_2") (pintype "passive"))
      (node (ref "R26") (pin "1") (pinfunction "1_1") (pintype "passive"))
    )
    (net (code "51") (name "Net-(Q6-C)") (class "Default")
      (node (ref "Q6") (pin "3") (pinfunction "C_3") (pintype "passive"))
      (node (ref "R16") (pin "1") (pinfunction "1_1") (pintype "passive"))
    )
    (net (code "52") (name "Net-(Q7-G)") (class "Default")
      (node (ref "Q7") (pin "4") (pinfunction "G_4") (pintype "passive"))
      (node (ref "R20") (pin "2") (pinfunction "2_2") (pintype "passive"))
    )
    (net (code "53") (name "Net-(Q8-G)") (class "Default")
      (node (ref "Q8") (pin "4") (pinfunction "G_4") (pintype "passive"))
      (node (ref "R22") (pin "2") (pinfunction "2_2") (pintype "passive"))
    )
    (net (code "54") (name "Net-(Q9-B)") (class "Default")
      (node (ref "Q9") (pin "1") (pinfunction "B_1") (pintype "passive"))
      (node (ref "R34") (pin "2") (pinfunction "2_2") (pintype "passive"))
      (node (ref "R35") (pin "1") (pinfunction "1_1") (pintype "passive"))
    )
    (net (code "55") (name "Net-(Q9-C)") (class "Default")
      (node (ref "Q9") (pin "3") (pinfunction "C_3") (pintype "passive"))
      (node (ref "R33") (pin "1") (pinfunction "1_1") (pintype "passive"))
    )
    (net (code "56") (name "Net-(Q10-G)") (class "Default")
      (node (ref "Q10") (pin "4") (pinfunction "G_4") (pintype "passive"))
      (node (ref "R44") (pin "2") (pinfunction "2_2") (pintype "passive"))
    )
    (net (code "57") (name "Net-(Q11-G)") (class "Default")
      (node (ref "Q11") (pin "4") (pinfunction "G_4") (pintype "passive"))
      (node (ref "R46") (pin "2") (pinfunction "2_2") (pintype "passive"))
    )
    (net (code "58") (name "Net-(U3A-A)") (class "Default")
      (node (ref "R17") (pin "2") (pinfunction "2_2") (pintype "passive"))
      (node (ref "R19") (pin "1") (pinfunction "1_1") (pintype "passive"))
      (node (ref "U3") (pin "1") (pinfunction "A_1") (pintype "input"))
    )
    (net (code "59") (name "Net-(U3A-Y)") (class "Default")
      (node (ref "R20") (pin "1") (pinfunction "1_1") (pintype "passive"))
      (node (ref "U3") (pin "2") (pinfunction "Y_2") (pintype "output"))
    )
    (net (code "60") (name "Net-(U3B-A)") (class "Default")
      (node (ref "R18") (pin "2") (pinfunction "2_2") (pintype "passive"))
      (node (ref "R21") (pin "1") (pinfunction "1_1") (pintype "passive"))
      (node (ref "U3") (pin "3") (pinfunction "A_3") (pintype "input"))
    )
    (net (code "61") (name "Net-(U3B-Y)") (class "Default")
      (node (ref "R22") (pin "1") (pinfunction "1_1") (pintype "passive"))
      (node (ref "U3") (pin "4") (pinfunction "Y_4") (pintype "output"))
    )
    (net (code "62") (name "Net-(U3C-A)") (class "Default")
      (node (ref "R39") (pin "2") (pinfunction "2_2") (pintype "passive"))
      (node (ref "R43") (pin "1") (pinfunction "1_1") (pintype "passive"))
      (node (ref "U3") (pin "5") (pinfunction "A_5") (pintype "input"))
    )
    (net (code "63") (name "Net-(U3C-Y)") (class "Default")
      (node (ref "R44") (pin "1") (pinfunction "1_1") (pintype "passive"))
      (node (ref "U3") (pin "6") (pinfunction "Y_6") (pintype "output"))
    )
    (net (code "64") (name "Net-(U3D-A)") (class "Default")
      (node (ref "R40") (pin "2") (pinfunction "2_2") (pintype "passive"))
      (node (ref "R45") (pin "1") (pinfunction "1_1") (pintype "passive"))
      (node (ref "U3") (pin "9") (pinfunction "A_9") (pintype "input"))
    )
    (net (code "65") (name "Net-(U3D-Y)") (class "Default")
      (node (ref "R46") (pin "1") (pinfunction "1_1") (pintype "passive"))
      (node (ref "U3") (pin "8") (pinfunction "Y_8") (pintype "output"))
    )
    (net (code "66") (name "PGND") (class "Default")
      (node (ref "BAT") (pin "1") (pinfunction "1_1") (pintype "passive"))
      (node (ref "D10") (pin "1") (pinfunction "A_1") (pintype "passive"))
      (node (ref "D4") (pin "2") (pinfunction "K_2") (pintype "passive"))
      (node (ref "D6") (pin "1") (pinfunction "A_1") (pintype "passive"))
      (node (ref "D7") (pin "1") (pinfunction "A_1") (pintype "passive"))
      (node (ref "D9") (pin "1") (pinfunction "A_1") (pintype "passive"))
      (node (ref "Q10") (pin "1") (pinfunction "S_1") (pintype "passive"))
      (node (ref "Q10") (pin "2") (pinfunction "S_2") (pintype "passive"))
      (node (ref "Q10") (pin "3") (pinfunction "S_3") (pintype "passive"))
      (node (ref "Q11") (pin "1") (pinfunction "S_1") (pintype "passive"))
      (node (ref "Q11") (pin "2") (pinfunction "S_2") (pintype "passive"))
      (node (ref "Q11") (pin "3") (pinfunction "S_3") (pintype "passive"))
      (node (ref "Q4") (pin "2") (pinfunction "E_2") (pintype "passive"))
      (node (ref "Q5") (pin "2") (pinfunction "E_2") (pintype "passive"))
      (node (ref "Q7") (pin "1") (pinfunction "S_1") (pintype "passive"))
      (node (ref "Q7") (pin "2") (pinfunction "S_2") (pintype "passive"))
      (node (ref "Q7") (pin "3") (pinfunction "S_3") (pintype "passive"))
      (node (ref "Q8") (pin "1") (pinfunction "S_1") (pintype "passive"))
      (node (ref "Q8") (pin "2") (pinfunction "S_2") (pintype "passive"))
      (node (ref "Q8") (pin "3") (pinfunction "S_3") (pintype "passive"))
      (node (ref "R11") (pin "1") (pinfunction "1_1") (pintype "passive"))
      (node (ref "R12") (pin "2") (pinfunction "2_2") (pintype "passive"))
      (node (ref "R13") (pin "1") (pinfunction "1_1") (pintype "passive"))
      (node (ref "R3") (pin "2") (pinfunction "2_2") (pintype "passive"))
      (node (ref "R4") (pin "2") (pinfunction "2_2") (pintype "passive"))
    )
    (net (code "67") (name "VCC5V") (class "Default")
      (node (ref "C10") (pin "2") (pinfunction "2_2") (pintype "passive"))
      (node (ref "C11") (pin "2") (pinfunction "2_2") (pintype "passive"))
      (node (ref "C12") (pin "2") (pinfunction "2_2") (pintype "passive"))
      (node (ref "C13") (pin "2") (pinfunction "2_2") (pintype "passive"))
      (node (ref "C14") (pin "2") (pinfunction "2_2") (pintype "passive"))
      (node (ref "C15") (pin "2") (pinfunction "2_2") (pintype "passive"))
      (node (ref "C18") (pin "2") (pinfunction "2_2") (pintype "passive"))
      (node (ref "C2") (pin "1") (pinfunction "1_1") (pintype "passive"))
      (node (ref "C20") (pin "2") (pinfunction "2_2") (pintype "passive"))
      (node (ref "C4") (pin "2") (pinfunction "2_2") (pintype "passive"))
      (node (ref "C6") (pin "2") (pinfunction "2_2") (pintype "passive"))
      (node (ref "C7") (pin "2") (pinfunction "2_2") (pintype "passive"))
      (node (ref "D5") (pin "A") (pinfunction "A_A") (pintype "passive"))
      (node (ref "D8") (pin "A") (pinfunction "A_A") (pintype "passive"))
      (node (ref "P4") (pin "2") (pinfunction "2_2") (pintype "passive"))
      (node (ref "P4") (pin "4") (pinfunction "4_4") (pintype "passive"))
      (node (ref "R1") (pin "1") (pinfunction "1_1") (pintype "passive"))
      (node (ref "R14") (pin "1") (pinfunction "1_1") (pintype "passive"))
      (node (ref "R17") (pin "1") (pinfunction "1_1") (pintype "passive"))
      (node (ref "R18") (pin "1") (pinfunction "1_1") (pintype "passive"))
      (node (ref "R2") (pin "1") (pinfunction "1_1") (pintype "passive"))
      (node (ref "R24") (pin "2") (pinfunction "2_2") (pintype "passive"))
      (node (ref "R25") (pin "2") (pinfunction "2_2") (pintype "passive"))
      (node (ref "R27") (pin "2") (pinfunction "2_2") (pintype "passive"))
      (node (ref "R28") (pin "2") (pinfunction "2_2") (pintype "passive"))
      (node (ref "R29") (pin "2") (pinfunction "2_2") (pintype "passive"))
      (node (ref "R30") (pin "2") (pinfunction "2_2") (pintype "passive"))
      (node (ref "R31") (pin "2") (pinfunction "2_2") (pintype "passive"))
      (node (ref "R32") (pin "2") (pinfunction "2_2") (pintype "passive"))
      (node (ref "R39") (pin "1") (pinfunction "1_1") (pintype "passive"))
      (node (ref "R40") (pin "1") (pinfunction "1_1") (pintype "passive"))
      (node (ref "R42") (pin "1") (pinfunction "1_1") (pintype "passive"))
      (node (ref "R48") (pin "2") (pinfunction "2_2") (pintype "passive"))
      (node (ref "R49") (pin "1") (pinfunction "1_1") (pintype "passive"))
      (node (ref "R50") (pin "2") (pinfunction "2_2") (pintype "passive"))
      (node (ref "R51") (pin "1") (pinfunction "1_1") (pintype "passive"))
      (node (ref "R52") (pin "1") (pinfunction "1_1") (pintype "passive"))
      (node (ref "T1") (pin "1") (pinfunction "1_1") (pintype "passive"))
      (node (ref "T2") (pin "1") (pinfunction "1_1") (pintype "passive"))
      (node (ref "T3") (pin "1") (pinfunction "1_1") (pintype "passive"))
      (node (ref "T4") (pin "1") (pinfunction "1_1") (pintype "passive"))
      (node (ref "T5") (pin "1") (pinfunction "1_1") (pintype "passive"))
      (node (ref "T6") (pin "1") (pinfunction "1_1") (pintype "passive"))
      (node (ref "U1") (pin "3") (pinfunction "VOUT_3") (pintype "passive"))
      (node (ref "U2") (pin "24") (pinfunction "VCC_24") (pintype "passive"))
      (node (ref "U3") (pin "14") (pinfunction "VDD_14") (pintype "power_in"))
      (node (ref "U5") (pin "5") (pinfunction "AIN1_5") (pintype "input"))
      (node (ref "U5") (pin "8") (pinfunction "VDD_8") (pintype "power_in"))
      (node (ref "U7") (pin "1") (pinfunction "VCC_1") (pintype "passive"))
    )
    (net (code "68") (name "VCC12V") (class "Default")
      (node (ref "C1") (pin "1") (pinfunction "1_1") (pintype "passive"))
      (node (ref "FAN1") (pin "1") (pinfunction "1_1") (pintype "passive"))
      (node (ref "FAN2") (pin "1") (pinfunction "1_1") (pintype "passive"))
      (node (ref "FAN3") (pin "1") (pinfunction "1_1") (pintype "passive"))
      (node (ref "FAN4") (pin "1") (pinfunction "1_1") (pintype "passive"))
      (node (ref "FAN5") (pin "1") (pinfunction "1_1") (pintype "passive"))
      (node (ref "FAN6") (pin "1") (pinfunction "1_1") (pintype "passive"))
      (node (ref "FAN7") (pin "1") (pinfunction "1_1") (pintype "passive"))
      (node (ref "FAN8") (pin "1") (pinfunction "1_1") (pintype "passive"))
      (node (ref "Q2") (pin "2") (pinfunction "D_2") (pintype "passive"))
      (node (ref "U1") (pin "1") (pinfunction "VIN_1") (pintype "passive"))
    )
    (net (code "69") (name "unconnected-(P4-Pad1)") (class "Default")
      (node (ref "P4") (pin "1") (pinfunction "1_1") (pintype "passive"))
    )
    (net (code "70") (name "unconnected-(P4-Pad15)") (class "Default")
      (node (ref "P4") (pin "15") (pinfunction "15_15") (pintype "passive"))
    )
    (net (code "71") (name "unconnected-(P4-Pad16)") (class "Default")
      (node (ref "P4") (pin "16") (pinfunction "16_16") (pintype "passive"))
    )
    (net (code "72") (name "unconnected-(P4-Pad17)") (class "Default")
      (node (ref "P4") (pin "17") (pinfunction "17_17") (pintype "passive"))
    )
    (net (code "73") (name "unconnected-(P4-Pad18)") (class "Default")
      (node (ref "P4") (pin "18") (pinfunction "18_18") (pintype "passive"))
    )
    (net (code "74") (name "unconnected-(P4-Pad19)") (class "Default")
      (node (ref "P4") (pin "19") (pinfunction "19_19") (pintype "passive"))
    )
    (net (code "75") (name "unconnected-(P4-Pad21)") (class "Default")
      (node (ref "P4") (pin "21") (pinfunction "21_21") (pintype "passive"))
    )
    (net (code "76") (name "unconnected-(P4-Pad22)") (class "Default")
      (node (ref "P4") (pin "22") (pinfunction "22_22") (pintype "passive"))
    )
    (net (code "77") (name "unconnected-(P4-Pad23)") (class "Default")
      (node (ref "P4") (pin "23") (pinfunction "23_23") (pintype "passive"))
    )
    (net (code "78") (name "unconnected-(P4-Pad24)") (class "Default")
      (node (ref "P4") (pin "24") (pinfunction "24_24") (pintype "passive"))
    )
    (net (code "79") (name "unconnected-(P4-Pad26)") (class "Default")
      (node (ref "P4") (pin "26") (pinfunction "26_26") (pintype "passive"))
    )
    (net (code "80") (name "unconnected-(P4-Pad27)") (class "Default")
      (node (ref "P4") (pin "27") (pinfunction "27_27") (pintype "passive"))
    )
    (net (code "81") (name "unconnected-(P4-Pad28)") (class "Default")
      (node (ref "P4") (pin "28") (pinfunction "28_28") (pintype "passive"))
    )
    (net (code "82") (name "unconnected-(P4-Pad29)") (class "Default")
      (node (ref "P4") (pin "29") (pinfunction "29_29") (pintype "passive"))
    )
    (net (code "83") (name "unconnected-(P4-Pad31)") (class "Default")
      (node (ref "P4") (pin "31") (pinfunction "31_31") (pintype "passive"))
    )
    (net (code "84") (name "unconnected-(P4-Pad36)") (class "Default")
      (node (ref "P4") (pin "36") (pinfunction "36_36") (pintype "passive"))
    )
    (net (code "85") (name "unconnected-(P4-Pad37)") (class "Default")
      (node (ref "P4") (pin "37") (pinfunction "37_37") (pintype "passive"))
    )
    (net (code "86") (name "unconnected-(P4-Pad38)") (class "Default")
      (node (ref "P4") (pin "38") (pinfunction "38_38") (pintype "passive"))
    )
    (net (code "87") (name "unconnected-(P4-Pad40)") (class "Default")
      (node (ref "P4") (pin "40") (pinfunction "40_40") (pintype "passive"))
    )
    (net (code "88") (name "unconnected-(S1-Pad3)") (class "Default")
      (node (ref "S1") (pin "3") (pinfunction "3_3") (pintype "passive"))
    )
    (net (code "89") (name "unconnected-(S1-Pad4)") (class "Default")
      (node (ref "S1") (pin "4") (pinfunction "4_4") (pintype "passive"))
    )
    (net (code "90") (name "unconnected-(S1-Pad5)") (class "Default")
      (node (ref "S1") (pin "5") (pinfunction "5_5") (pintype "passive"))
    )
    (net (code "91") (name "unconnected-(S1-Pad6)") (class "Default")
      (node (ref "S1") (pin "6") (pinfunction "6_6") (pintype "passive"))
    )
    (net (code "92") (name "unconnected-(U1-EN-Pad5)") (class "Default")
      (node (ref "U1") (pin "5") (pinfunction "EN_5") (pintype "passive"))
    )
    (net (code "93") (name "unconnected-(U1-FB-Pad6)") (class "Default")
      (node (ref "U1") (pin "6") (pinfunction "FB_6") (pintype "passive"))
    )
    (net (code "94") (name "unconnected-(U1-NC-Pad4)") (class "Default")
      (node (ref "U1") (pin "4") (pinfunction "NC_4") (pintype "passive"))
    )
    (net (code "95") (name "unconnected-(U2-SC0-Pad5)") (class "Default")
      (node (ref "U2") (pin "5") (pinfunction "SC0_5") (pintype "passive"))
    )
    (net (code "96") (name "unconnected-(U2-SD0-Pad4)") (class "Default")
      (node (ref "U2") (pin "4") (pinfunction "SD0_4") (pintype "passive"))
    )
    (net (code "97") (name "unconnected-(U3E-Y-Pad10)") (class "Default")
      (node (ref "U3") (pin "10") (pinfunction "Y_10") (pintype "output"))
    )
    (net (code "98") (name "unconnected-(U3F-Y-Pad12)") (class "Default")
      (node (ref "U3") (pin "12") (pinfunction "Y_12") (pintype "output"))
    )
    (net (code "99") (name "unconnected-(U5-ALERT_RDY-Pad2)") (class "Default")
      (node (ref "U5") (pin "2") (pinfunction "ALERT_RDY_2") (pintype "output"))
    )
  )
)
